# FDL-1_BSTP_v1_0.net
KiCad netlist of a schematic drawn in EAGLE
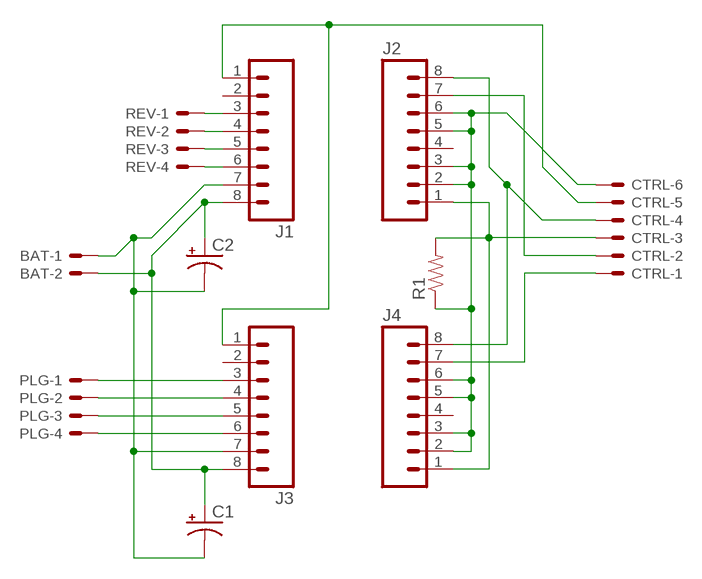
[diagram p0: schematic, sheet 1]

(export (version "E")
  (design (tool "Eeschema 10.0.6"))
  (components
    (comp (ref "BAT")
      (value "JST-XH-02-PIN-LONG-PAD")
      (footprint "eagle-import:JST-XH-02-PACKAGE-LONG-PAD")
      (libsource (lib "eagle-import") (part "JST-XH-02-PIN-LONG-PAD"))
    )
    (comp (ref "C1")
      (value "CAP_POLPTH1")
      (footprint "eagle-import:CPOL-RADIAL-100UF-25V")
      (libsource (lib "eagle-import") (part "CAP_POLPTH1"))
    )
    (comp (ref "C2")
      (value "CAP_POLPTH1")
      (footprint "eagle-import:CPOL-RADIAL-100UF-25V")
      (libsource (lib "eagle-import") (part "CAP_POLPTH1"))
    )
    (comp (ref "CTRL")
      (value "JST-XH-06-PIN-LONG-PAD")
      (footprint "eagle-import:JST-XH-06-PACKAGE-LONG-PAD")
      (libsource (lib "eagle-import") (part "JST-XH-06-PIN-LONG-PAD"))
    )
    (comp (ref "J1")
      (value "M08SILK_FEMALE_PTH")
      (footprint "eagle-import:1X08")
      (libsource (lib "eagle-import") (part "M08SILK_FEMALE_PTH"))
    )
    (comp (ref "J2")
      (value "M08SILK_FEMALE_PTH")
      (footprint "eagle-import:1X08")
      (libsource (lib "eagle-import") (part "M08SILK_FEMALE_PTH"))
    )
    (comp (ref "J3")
      (value "M08SILK_FEMALE_PTH")
      (footprint "eagle-import:1X08")
      (libsource (lib "eagle-import") (part "M08SILK_FEMALE_PTH"))
    )
    (comp (ref "J4")
      (value "M08SILK_FEMALE_PTH")
      (footprint "eagle-import:1X08")
      (libsource (lib "eagle-import") (part "M08SILK_FEMALE_PTH"))
    )
    (comp (ref "PLG")
      (value "JST-XH-04-PIN-LONG-PAD")
      (footprint "eagle-import:JST-XH-04-PACKAGE-LONG-PAD")
      (libsource (lib "eagle-import") (part "JST-XH-04-PIN-LONG-PAD"))
    )
    (comp (ref "R1")
      (value "RESISTORPTH-1/4W")
      (footprint "eagle-import:AXIAL-0.4")
      (libsource (lib "eagle-import") (part "RESISTORPTH-1/4W"))
    )
    (comp (ref "REV")
      (value "JST-XH-04-PIN-LONG-PAD")
      (footprint "eagle-import:JST-XH-04-PACKAGE-LONG-PAD")
      (libsource (lib "eagle-import") (part "JST-XH-04-PIN-LONG-PAD"))
    )
  )
  (nets
    (net (code "1") (name "Net-(BATA-S)") (class "Default")
      (node (ref "BAT") (pin "1") (pinfunction "S_1") (pintype "passive"))
      (node (ref "C1") (pin "2") (pinfunction "-_2") (pintype "passive"))
      (node (ref "C2") (pin "2") (pinfunction "-_2") (pintype "passive"))
      (node (ref "J1") (pin "7") (pinfunction "7_7") (pintype "passive"))
      (node (ref "J3") (pin "7") (pinfunction "7_7") (pintype "passive"))
    )
    (net (code "2") (name "Net-(BATB-S)") (class "Default")
      (node (ref "BAT") (pin "2") (pinfunction "S_2") (pintype "passive"))
      (node (ref "C1") (pin "1") (pinfunction "+_1") (pintype "passive"))
      (node (ref "C2") (pin "1") (pinfunction "+_1") (pintype "passive"))
      (node (ref "J1") (pin "8") (pinfunction "8_8") (pintype "passive"))
      (node (ref "J3") (pin "8") (pinfunction "8_8") (pintype "passive"))
    )
    (net (code "3") (name "Net-(CTRLA-S)") (class "Default")
      (node (ref "CTRL") (pin "1") (pinfunction "S_1") (pintype "passive"))
      (node (ref "J4") (pin "7") (pinfunction "7_7") (pintype "passive"))
    )
    (net (code "4") (name "Net-(CTRLB-S)") (class "Default")
      (node (ref "CTRL") (pin "2") (pinfunction "S_2") (pintype "passive"))
      (node (ref "J2") (pin "7") (pinfunction "7_7") (pintype "passive"))
    )
    (net (code "5") (name "Net-(CTRLC-S)") (class "Default")
      (node (ref "CTRL") (pin "3") (pinfunction "S_3") (pintype "passive"))
      (node (ref "J2") (pin "1") (pinfunction "1_1") (pintype "passive"))
      (node (ref "J4") (pin "1") (pinfunction "1_1") (pintype "passive"))
      (node (ref "R1") (pin "P$2") (pinfunction "2_P$2") (pintype "passive"))
    )
    (net (code "6") (name "Net-(CTRLD-S)") (class "Default")
      (node (ref "CTRL") (pin "4") (pinfunction "S_4") (pintype "passive"))
      (node (ref "J2") (pin "8") (pinfunction "8_8") (pintype "passive"))
      (node (ref "J4") (pin "8") (pinfunction "8_8") (pintype "passive"))
    )
    (net (code "7") (name "Net-(CTRLE-S)") (class "Default")
      (node (ref "CTRL") (pin "5") (pinfunction "S_5") (pintype "passive"))
      (node (ref "J1") (pin "1") (pinfunction "1_1") (pintype "passive"))
      (node (ref "J3") (pin "1") (pinfunction "1_1") (pintype "passive"))
    )
    (net (code "8") (name "Net-(CTRLF-S)") (class "Default")
      (node (ref "CTRL") (pin "6") (pinfunction "S_6") (pintype "passive"))
      (node (ref "J2") (pin "2") (pinfunction "2_2") (pintype "passive"))
      (node (ref "J2") (pin "3") (pinfunction "3_3") (pintype "passive"))
      (node (ref "J2") (pin "5") (pinfunction "5_5") (pintype "passive"))
      (node (ref "J2") (pin "6") (pinfunction "6_6") (pintype "passive"))
      (node (ref "J4") (pin "2") (pinfunction "2_2") (pintype "passive"))
      (node (ref "J4") (pin "3") (pinfunction "3_3") (pintype "passive"))
      (node (ref "J4") (pin "5") (pinfunction "5_5") (pintype "passive"))
      (node (ref "J4") (pin "6") (pinfunction "6_6") (pintype "passive"))
      (node (ref "R1") (pin "P$1") (pinfunction "1_P$1") (pintype "passive"))
    )
    (net (code "9") (name "Net-(PLGA-S)") (class "Default")
      (node (ref "J3") (pin "3") (pinfunction "3_3") (pintype "passive"))
      (node (ref "PLG") (pin "1") (pinfunction "S_1") (pintype "passive"))
    )
    (net (code "10") (name "Net-(PLGB-S)") (class "Default")
      (node (ref "J3") (pin "4") (pinfunction "4_4") (pintype "passive"))
      (node (ref "PLG") (pin "2") (pinfunction "S_2") (pintype "passive"))
    )
    (net (code "11") (name "Net-(PLGC-S)") (class "Default")
      (node (ref "J3") (pin "5") (pinfunction "5_5") (pintype "passive"))
      (node (ref "PLG") (pin "3") (pinfunction "S_3") (pintype "passive"))
    )
    (net (code "12") (name "Net-(PLGD-S)") (class "Default")
      (node (ref "J3") (pin "6") (pinfunction "6_6") (pintype "passive"))
      (node (ref "PLG") (pin "4") (pinfunction "S_4") (pintype "passive"))
    )
    (net (code "13") (name "Net-(REVA-S)") (class "Default")
      (node (ref "J1") (pin "3") (pinfunction "3_3") (pintype "passive"))
      (node (ref "REV") (pin "1") (pinfunction "S_1") (pintype "passive"))
    )
    (net (code "14") (name "Net-(REVB-S)") (class "Default")
      (node (ref "J1") (pin "4") (pinfunction "4_4") (pintype "passive"))
      (node (ref "REV") (pin "2") (pinfunction "S_2") (pintype "passive"))
    )
    (net (code "15") (name "Net-(REVC-S)") (class "Default")
      (node (ref "J1") (pin "5") (pinfunction "5_5") (pintype "passive"))
      (node (ref "REV") (pin "3") (pinfunction "S_3") (pintype "passive"))
    )
    (net (code "16") (name "Net-(REVD-S)") (class "Default")
      (node (ref "J1") (pin "6") (pinfunction "6_6") (pintype "passive"))
      (node (ref "REV") (pin "4") (pinfunction "S_4") (pintype "passive"))
    )
    (net (code "17") (name "unconnected-(J1-Pad2)") (class "Default")
      (node (ref "J1") (pin "2") (pinfunction "2_2") (pintype "passive"))
    )
    (net (code "18") (name "unconnected-(J2-Pad4)") (class "Default")
      (node (ref "J2") (pin "4") (pinfunction "4_4") (pintype "passive"))
    )
    (net (code "19") (name "unconnected-(J3-Pad2)") (class "Default")
      (node (ref "J3") (pin "2") (pinfunction "2_2") (pintype "passive"))
    )
    (net (code "20") (name "unconnected-(J4-Pad4)") (class "Default")
      (node (ref "J4") (pin "4") (pinfunction "4_4") (pintype "passive"))
    )
  )
)
